# AcceleratedLED.net
KiCad netlist of a schematic drawn in EAGLE
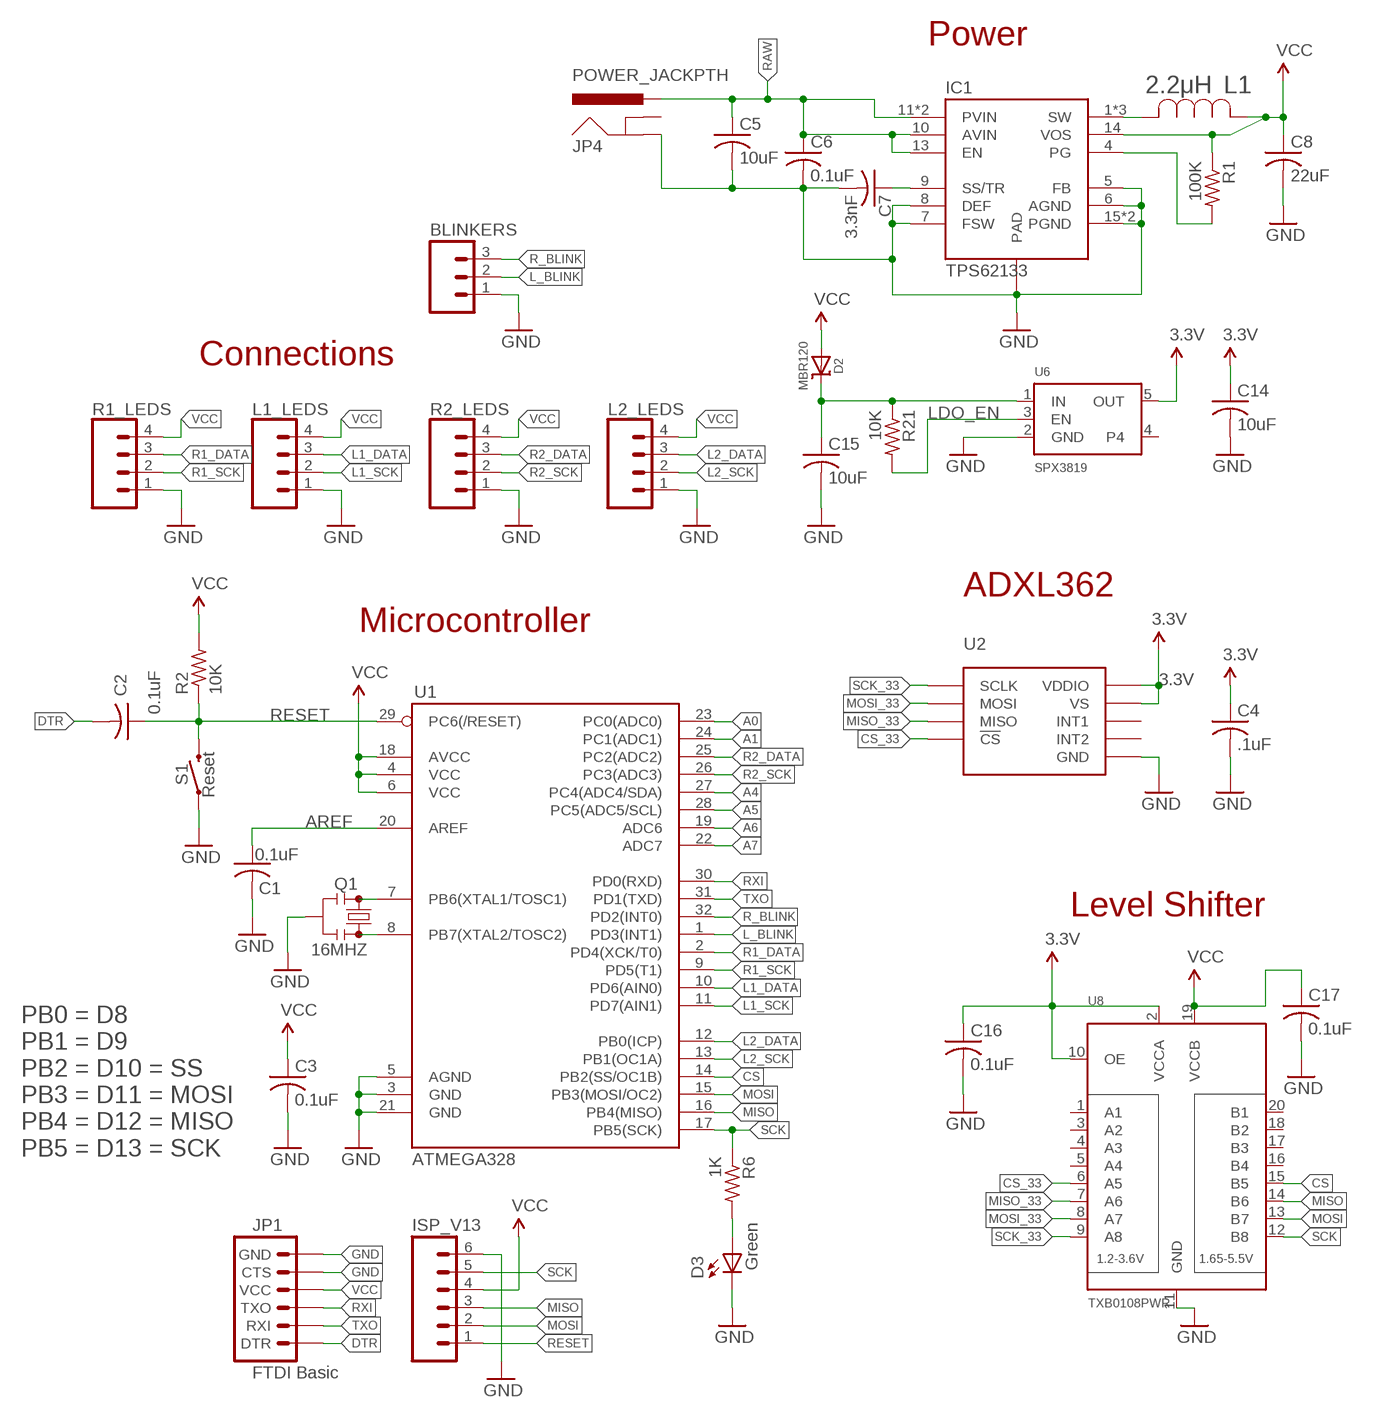
[diagram p0: schematic, sheet 1]

(export (version "E")
  (design (tool "Eeschema 10.0.6"))
  (components
    (comp (ref "BLINKERS")
      (value "M03JST-PTH")
      (footprint "eagle-import:JST-3-PTH")
      (libsource (lib "eagle-import") (part "M03JST-PTH"))
    )
    (comp (ref "C1")
      (value "0.1uF")
      (footprint "eagle-import:C0805")
      (libsource (lib "eagle-import") (part "C-USC0805"))
    )
    (comp (ref "C2")
      (value "0.1uF")
      (footprint "eagle-import:C0805")
      (libsource (lib "eagle-import") (part "C-USC0805"))
    )
    (comp (ref "C3")
      (value "0.1uF")
      (footprint "eagle-import:C0805")
      (libsource (lib "eagle-import") (part "C-USC0805"))
    )
    (comp (ref "C4")
      (value ".1uF")
      (footprint "eagle-import:C0805")
      (libsource (lib "eagle-import") (part "RemoteMotion_2810894_C-USC0805"))
    )
    (comp (ref "C5")
      (value "10uF")
      (footprint "eagle-import:C0805")
      (libsource (lib "eagle-import") (part "RemoteMotion_2810894_C-USC0805"))
    )
    (comp (ref "C6")
      (value "0.1uF")
      (footprint "eagle-import:C0805")
      (libsource (lib "eagle-import") (part "C-USC0805"))
    )
    (comp (ref "C7")
      (value "3.3nF")
      (footprint "eagle-import:C0805")
      (libsource (lib "eagle-import") (part "C-USC0805"))
    )
    (comp (ref "C8")
      (value "22uF")
      (footprint "eagle-import:C0805")
      (libsource (lib "eagle-import") (part "RemoteMotion_2810894_C-USC0805"))
    )
    (comp (ref "C14")
      (value "10uF")
      (footprint "eagle-import:C0805")
      (libsource (lib "eagle-import") (part "RemoteMotion_2810894_C-USC0805"))
    )
    (comp (ref "C15")
      (value "10uF")
      (footprint "eagle-import:C0805")
      (libsource (lib "eagle-import") (part "C-USC0805"))
    )
    (comp (ref "C16")
      (value "0.1uF")
      (footprint "eagle-import:C0805")
      (libsource (lib "eagle-import") (part "rcl_334_C-USC0805"))
    )
    (comp (ref "C17")
      (value "0.1uF")
      (footprint "eagle-import:C0805")
      (libsource (lib "eagle-import") (part "rcl_334_C-USC0805"))
    )
    (comp (ref "D2")
      (value "MBR120")
      (footprint "eagle-import:SOD-123")
      (libsource (lib "eagle-import") (part "DIODE-SCHOTTKYSOD-123"))
    )
    (comp (ref "D3")
      (value "Green")
      (footprint "eagle-import:CHIPLED_0805")
      (libsource (lib "eagle-import") (part "LEDCHIPLED_0805"))
    )
    (comp (ref "IC1")
      (value "TPS62133")
      (footprint "eagle-import:QFN16")
      (libsource (lib "eagle-import") (part "TPS62133"))
    )
    (comp (ref "ISP_V13")
      (value "M06SIP")
      (footprint "eagle-import:1X06")
      (libsource (lib "eagle-import") (part "M06SIP"))
    )
    (comp (ref "JP1")
      (value "FTDI Basic")
      (footprint "eagle-import:1X06")
      (libsource (lib "eagle-import") (part "ARDUINO_SERIAL_PROGRAMPTH"))
    )
    (comp (ref "JP4")
      (value "POWER_JACKPTH")
      (footprint "eagle-import:POWER_JACK_PTH")
      (libsource (lib "eagle-import") (part "POWER_JACKPTH"))
    )
    (comp (ref "L1")
      (value "2.2μH")
      (footprint "eagle-import:IND_IHLP-1212BZ-L")
      (fields (field (name "MANUFACTURER_PART_NUMBER") "IHLP1212BZER2R2M11"))
      (libsource (lib "eagle-import") (part "IHLP1212BZER2R2M11IND_IHLP-1212BZ-L"))
    )
    (comp (ref "L1_LEDS")
      (value "CONN_04JST-PTH")
      (footprint "eagle-import:JST-4-PTH")
      (libsource (lib "eagle-import") (part "CONN_04JST-PTH"))
    )
    (comp (ref "L2_LEDS")
      (value "CONN_04JST-PTH")
      (footprint "eagle-import:JST-4-PTH")
      (libsource (lib "eagle-import") (part "CONN_04JST-PTH"))
    )
    (comp (ref "Q1")
      (value "16MHZ")
      (footprint "eagle-import:RESONATOR-SMD")
      (libsource (lib "eagle-import") (part "RESONATOR16MHZ"))
    )
    (comp (ref "R1")
      (value "100K")
      (footprint "eagle-import:M0805")
      (libsource (lib "eagle-import") (part "R-US_M0805"))
    )
    (comp (ref "R1_LEDS")
      (value "CONN_04JST-PTH")
      (footprint "eagle-import:JST-4-PTH")
      (libsource (lib "eagle-import") (part "CONN_04JST-PTH"))
    )
    (comp (ref "R2")
      (value "10K")
      (footprint "eagle-import:M0805")
      (libsource (lib "eagle-import") (part "R-US_M0805"))
    )
    (comp (ref "R2_LEDS")
      (value "CONN_04JST-PTH")
      (footprint "eagle-import:JST-4-PTH")
      (libsource (lib "eagle-import") (part "CONN_04JST-PTH"))
    )
    (comp (ref "R6")
      (value "1K")
      (footprint "eagle-import:M0805")
      (libsource (lib "eagle-import") (part "R-US_M0805"))
    )
    (comp (ref "R21")
      (value "10K")
      (footprint "eagle-import:M0805")
      (libsource (lib "eagle-import") (part "R-US_M0805"))
    )
    (comp (ref "S1")
      (value "Reset")
      (footprint "eagle-import:TACTILE_SWITCH_SMD_5.2MM")
      (libsource (lib "eagle-import") (part "MOMENTARY-SWITCH-SPST-SMD-5.2-REDUNDANT"))
    )
    (comp (ref "U1")
      (value "ATMEGA328")
      (footprint "eagle-import:TQFP32-08")
      (libsource (lib "eagle-import") (part "ATMEGA168"))
    )
    (comp (ref "U2")
      (value "ADXL362ADXL362-1:1")
      (footprint "eagle-import:ADXL362-1_1")
      (libsource (lib "eagle-import") (part "ADXL362ADXL362-1{colon}1"))
    )
    (comp (ref "U6")
      (value "SPX3819")
      (footprint "eagle-import:SOT23-5")
      (libsource (lib "eagle-import") (part "VREG_SOT23-5"))
    )
    (comp (ref "U8")
      (value "TXB0108PWR")
      (footprint "eagle-import:TSSOP20")
      (libsource (lib "eagle-import") (part "TXB0108PWR"))
    )
  )
  (nets
    (net (code "1") (name "/AREF") (class "Default")
      (node (ref "C1") (pin "1") (pinfunction "1_1") (pintype "passive"))
      (node (ref "U1") (pin "20") (pinfunction "AREF_20") (pintype "bidirectional"))
    )
    (net (code "2") (name "/LDO_EN") (class "Default")
      (node (ref "R21") (pin "2") (pinfunction "2_2") (pintype "passive"))
      (node (ref "U6") (pin "3") (pinfunction "EN_3") (pintype "input"))
    )
    (net (code "3") (name "3.3V") (class "Default")
      (node (ref "C14") (pin "1") (pinfunction "1_1") (pintype "passive"))
      (node (ref "C16") (pin "1") (pinfunction "1_1") (pintype "passive"))
      (node (ref "C4") (pin "1") (pinfunction "1_1") (pintype "passive"))
      (node (ref "U2") (pin "P$1") (pinfunction "VDDIO_P$1") (pintype "bidirectional"))
      (node (ref "U2") (pin "P$14") (pinfunction "VS_P$14") (pintype "bidirectional"))
      (node (ref "U6") (pin "5") (pinfunction "OUT_5") (pintype "power_in"))
      (node (ref "U8") (pin "10") (pinfunction "OE_10") (pintype "bidirectional"))
      (node (ref "U8") (pin "2") (pinfunction "VCCA_2") (pintype "bidirectional"))
    )
    (net (code "4") (name "A0") (class "Default")
      (node (ref "U1") (pin "23") (pinfunction "PC0(ADC0)_23") (pintype "bidirectional"))
    )
    (net (code "5") (name "A1") (class "Default")
      (node (ref "U1") (pin "24") (pinfunction "PC1(ADC1)_24") (pintype "bidirectional"))
    )
    (net (code "6") (name "A4") (class "Default")
      (node (ref "U1") (pin "27") (pinfunction "PC4(ADC4/SDA)_27") (pintype "bidirectional"))
    )
    (net (code "7") (name "A5") (class "Default")
      (node (ref "U1") (pin "28") (pinfunction "PC5(ADC5/SCL)_28") (pintype "bidirectional"))
    )
    (net (code "8") (name "A6") (class "Default")
      (node (ref "U1") (pin "19") (pinfunction "ADC6_19") (pintype "bidirectional"))
    )
    (net (code "9") (name "A7") (class "Default")
      (node (ref "U1") (pin "22") (pinfunction "ADC7_22") (pintype "bidirectional"))
    )
    (net (code "10") (name "CS") (class "Default")
      (node (ref "U1") (pin "14") (pinfunction "PB2(SS/OC1B)_14") (pintype "bidirectional"))
      (node (ref "U8") (pin "15") (pinfunction "B5_15") (pintype "bidirectional"))
    )
    (net (code "11") (name "CS_33") (class "Default")
      (node (ref "U2") (pin "P$8") (pinfunction "~{CS}_P$8") (pintype "bidirectional"))
      (node (ref "U8") (pin "6") (pinfunction "A5_6") (pintype "bidirectional"))
    )
    (net (code "12") (name "DTR") (class "Default")
      (node (ref "C2") (pin "2") (pinfunction "2_2") (pintype "passive"))
      (node (ref "JP1") (pin "1") (pinfunction "DTR_1") (pintype "passive"))
    )
    (net (code "13") (name "GND") (class "Default")
      (node (ref "BLINKERS") (pin "1") (pinfunction "1_1") (pintype "passive"))
      (node (ref "C1") (pin "2") (pinfunction "2_2") (pintype "passive"))
      (node (ref "C14") (pin "2") (pinfunction "2_2") (pintype "passive"))
      (node (ref "C15") (pin "2") (pinfunction "2_2") (pintype "passive"))
      (node (ref "C16") (pin "2") (pinfunction "2_2") (pintype "passive"))
      (node (ref "C17") (pin "2") (pinfunction "2_2") (pintype "passive"))
      (node (ref "C3") (pin "2") (pinfunction "2_2") (pintype "passive"))
      (node (ref "C4") (pin "2") (pinfunction "2_2") (pintype "passive"))
      (node (ref "C5") (pin "2") (pinfunction "2_2") (pintype "passive"))
      (node (ref "C6") (pin "2") (pinfunction "2_2") (pintype "passive"))
      (node (ref "C7") (pin "2") (pinfunction "2_2") (pintype "passive"))
      (node (ref "C8") (pin "2") (pinfunction "2_2") (pintype "passive"))
      (node (ref "D3") (pin "C") (pinfunction "C_C") (pintype "passive"))
      (node (ref "IC1") (pin "15") (pinfunction "PGND_15") (pintype "bidirectional"))
      (node (ref "IC1") (pin "16") (pinfunction "PGND_16") (pintype "bidirectional"))
      (node (ref "IC1") (pin "5") (pinfunction "FB_5") (pintype "bidirectional"))
      (node (ref "IC1") (pin "6") (pinfunction "AGND_6") (pintype "bidirectional"))
      (node (ref "IC1") (pin "7") (pinfunction "FSW_7") (pintype "bidirectional"))
      (node (ref "IC1") (pin "8") (pinfunction "DEF_8") (pintype "bidirectional"))
      (node (ref "IC1") (pin "PAD") (pinfunction "PAD_PAD") (pintype "bidirectional"))
      (node (ref "ISP_V13") (pin "6") (pinfunction "6_6") (pintype "passive"))
      (node (ref "JP1") (pin "5") (pinfunction "CTS_5") (pintype "passive"))
      (node (ref "JP1") (pin "6") (pinfunction "GND_6") (pintype "passive"))
      (node (ref "JP4") (pin "GND") (pinfunction "GND_GND") (pintype "bidirectional"))
      (node (ref "L1_LEDS") (pin "1") (pinfunction "1_1") (pintype "passive"))
      (node (ref "L2_LEDS") (pin "1") (pinfunction "1_1") (pintype "passive"))
      (node (ref "Q1") (pin "2") (pinfunction "2_2") (pintype "passive"))
      (node (ref "R1_LEDS") (pin "1") (pinfunction "1_1") (pintype "passive"))
      (node (ref "R2_LEDS") (pin "1") (pinfunction "1_1") (pintype "passive"))
      (node (ref "S1") (pin "1") (pinfunction "1_1") (pintype "passive"))
      (node (ref "S1") (pin "2") (pinfunction "1_2") (pintype "passive"))
      (node (ref "U1") (pin "21") (pinfunction "GND_21") (pintype "bidirectional"))
      (node (ref "U1") (pin "3") (pinfunction "GND_3") (pintype "bidirectional"))
      (node (ref "U1") (pin "5") (pinfunction "AGND_5") (pintype "bidirectional"))
      (node (ref "U2") (pin "P$12") (pinfunction "GND_P$12") (pintype "bidirectional"))
      (node (ref "U2") (pin "P$13") (pinfunction "GND_P$13") (pintype "bidirectional"))
      (node (ref "U2") (pin "P$16") (pinfunction "GND_P$16") (pintype "bidirectional"))
      (node (ref "U6") (pin "2") (pinfunction "GND_2") (pintype "power_in"))
      (node (ref "U8") (pin "11") (pinfunction "GND_11") (pintype "bidirectional"))
    )
    (net (code "14") (name "L1_DATA") (class "Default")
      (node (ref "L1_LEDS") (pin "3") (pinfunction "3_3") (pintype "passive"))
      (node (ref "U1") (pin "10") (pinfunction "PD6(AIN0)_10") (pintype "bidirectional"))
    )
    (net (code "15") (name "L1_SCK") (class "Default")
      (node (ref "L1_LEDS") (pin "2") (pinfunction "2_2") (pintype "passive"))
      (node (ref "U1") (pin "11") (pinfunction "PD7(AIN1)_11") (pintype "bidirectional"))
    )
    (net (code "16") (name "L2_DATA") (class "Default")
      (node (ref "L2_LEDS") (pin "3") (pinfunction "3_3") (pintype "passive"))
      (node (ref "U1") (pin "12") (pinfunction "PB0(ICP)_12") (pintype "bidirectional"))
    )
    (net (code "17") (name "L2_SCK") (class "Default")
      (node (ref "L2_LEDS") (pin "2") (pinfunction "2_2") (pintype "passive"))
      (node (ref "U1") (pin "13") (pinfunction "PB1(OC1A)_13") (pintype "bidirectional"))
    )
    (net (code "18") (name "L_BLINK") (class "Default")
      (node (ref "BLINKERS") (pin "2") (pinfunction "2_2") (pintype "passive"))
      (node (ref "U1") (pin "1") (pinfunction "PD3(INT1)_1") (pintype "bidirectional"))
    )
    (net (code "19") (name "MISO") (class "Default")
      (node (ref "ISP_V13") (pin "3") (pinfunction "3_3") (pintype "passive"))
      (node (ref "U1") (pin "16") (pinfunction "PB4(MISO)_16") (pintype "bidirectional"))
      (node (ref "U8") (pin "14") (pinfunction "B6_14") (pintype "bidirectional"))
    )
    (net (code "20") (name "MISO_33") (class "Default")
      (node (ref "U2") (pin "P$7") (pinfunction "MISO_P$7") (pintype "bidirectional"))
      (node (ref "U8") (pin "7") (pinfunction "A6_7") (pintype "bidirectional"))
    )
    (net (code "21") (name "MOSI") (class "Default")
      (node (ref "ISP_V13") (pin "2") (pinfunction "2_2") (pintype "passive"))
      (node (ref "U1") (pin "15") (pinfunction "PB3(MOSI/OC2)_15") (pintype "bidirectional"))
      (node (ref "U8") (pin "13") (pinfunction "B7_13") (pintype "bidirectional"))
    )
    (net (code "22") (name "MOSI_33") (class "Default")
      (node (ref "U2") (pin "P$6") (pinfunction "MOSI_P$6") (pintype "bidirectional"))
      (node (ref "U8") (pin "8") (pinfunction "A7_8") (pintype "bidirectional"))
    )
    (net (code "23") (name "Net-(D3-PadA)") (class "Default")
      (node (ref "D3") (pin "A") (pinfunction "A_A") (pintype "passive"))
      (node (ref "R6") (pin "2") (pinfunction "2_2") (pintype "passive"))
    )
    (net (code "24") (name "Net-(IC1-PG)") (class "Default")
      (node (ref "IC1") (pin "4") (pinfunction "PG_4") (pintype "bidirectional"))
      (node (ref "R1") (pin "2") (pinfunction "2_2") (pintype "passive"))
    )
    (net (code "25") (name "Net-(IC1-SS{slash}TR)") (class "Default")
      (node (ref "C7") (pin "1") (pinfunction "1_1") (pintype "passive"))
      (node (ref "IC1") (pin "9") (pinfunction "SS/TR_9") (pintype "bidirectional"))
    )
    (net (code "26") (name "Net-(IC1-SW-Pad1)") (class "Default")
      (node (ref "IC1") (pin "1") (pinfunction "SW_1") (pintype "bidirectional"))
      (node (ref "IC1") (pin "2") (pinfunction "SW_2") (pintype "bidirectional"))
      (node (ref "IC1") (pin "3") (pinfunction "SW_3") (pintype "bidirectional"))
      (node (ref "L1") (pin "2") (pinfunction "2_2") (pintype "passive"))
    )
    (net (code "27") (name "Net-(U1-PB6(XTAL1{slash}TOSC1))") (class "Default")
      (node (ref "Q1") (pin "1") (pinfunction "1_1") (pintype "passive"))
      (node (ref "U1") (pin "7") (pinfunction "PB6(XTAL1/TOSC1)_7") (pintype "bidirectional"))
    )
    (net (code "28") (name "Net-(U1-PB7(XTAL2{slash}TOSC2))") (class "Default")
      (node (ref "Q1") (pin "3") (pinfunction "3_3") (pintype "passive"))
      (node (ref "U1") (pin "8") (pinfunction "PB7(XTAL2/TOSC2)_8") (pintype "bidirectional"))
    )
    (net (code "29") (name "Net-(U6-IN)") (class "Default")
      (node (ref "C15") (pin "1") (pinfunction "1_1") (pintype "passive"))
      (node (ref "D2") (pin "C") (pinfunction "C_C") (pintype "passive"))
      (node (ref "R21") (pin "1") (pinfunction "1_1") (pintype "passive"))
      (node (ref "U6") (pin "1") (pinfunction "IN_1") (pintype "power_in"))
    )
    (net (code "30") (name "R1_DATA") (class "Default")
      (node (ref "R1_LEDS") (pin "3") (pinfunction "3_3") (pintype "passive"))
      (node (ref "U1") (pin "2") (pinfunction "PD4(XCK/T0)_2") (pintype "bidirectional"))
    )
    (net (code "31") (name "R1_SCK") (class "Default")
      (node (ref "R1_LEDS") (pin "2") (pinfunction "2_2") (pintype "passive"))
      (node (ref "U1") (pin "9") (pinfunction "PD5(T1)_9") (pintype "bidirectional"))
    )
    (net (code "32") (name "R2_DATA") (class "Default")
      (node (ref "R2_LEDS") (pin "3") (pinfunction "3_3") (pintype "passive"))
      (node (ref "U1") (pin "25") (pinfunction "PC2(ADC2)_25") (pintype "bidirectional"))
    )
    (net (code "33") (name "R2_SCK") (class "Default")
      (node (ref "R2_LEDS") (pin "2") (pinfunction "2_2") (pintype "passive"))
      (node (ref "U1") (pin "26") (pinfunction "PC3(ADC3)_26") (pintype "bidirectional"))
    )
    (net (code "34") (name "RAW") (class "Default")
      (node (ref "C5") (pin "1") (pinfunction "1_1") (pintype "passive"))
      (node (ref "C6") (pin "1") (pinfunction "1_1") (pintype "passive"))
      (node (ref "IC1") (pin "10") (pinfunction "AVIN_10") (pintype "bidirectional"))
      (node (ref "IC1") (pin "11") (pinfunction "PVIN_11") (pintype "bidirectional"))
      (node (ref "IC1") (pin "12") (pinfunction "PVIN_12") (pintype "bidirectional"))
      (node (ref "IC1") (pin "13") (pinfunction "EN_13") (pintype "bidirectional"))
      (node (ref "JP4") (pin "PWR") (pinfunction "PWR_PWR") (pintype "bidirectional"))
    )
    (net (code "35") (name "RESET") (class "Default")
      (node (ref "C2") (pin "1") (pinfunction "1_1") (pintype "passive"))
      (node (ref "ISP_V13") (pin "1") (pinfunction "1_1") (pintype "passive"))
      (node (ref "R2") (pin "1") (pinfunction "1_1") (pintype "passive"))
      (node (ref "S1") (pin "3") (pinfunction "2_3") (pintype "passive"))
      (node (ref "S1") (pin "4") (pinfunction "2_4") (pintype "passive"))
      (node (ref "U1") (pin "29") (pinfunction "PC6(/RESET)_29") (pintype "bidirectional"))
    )
    (net (code "36") (name "RXI") (class "Default")
      (node (ref "JP1") (pin "3") (pinfunction "TXO_3") (pintype "passive"))
      (node (ref "U1") (pin "30") (pinfunction "PD0(RXD)_30") (pintype "bidirectional"))
    )
    (net (code "37") (name "R_BLINK") (class "Default")
      (node (ref "BLINKERS") (pin "3") (pinfunction "3_3") (pintype "passive"))
      (node (ref "U1") (pin "32") (pinfunction "PD2(INT0)_32") (pintype "bidirectional"))
    )
    (net (code "38") (name "SCK") (class "Default")
      (node (ref "ISP_V13") (pin "5") (pinfunction "5_5") (pintype "passive"))
      (node (ref "R6") (pin "1") (pinfunction "1_1") (pintype "passive"))
      (node (ref "U1") (pin "17") (pinfunction "PB5(SCK)_17") (pintype "bidirectional"))
      (node (ref "U8") (pin "12") (pinfunction "B8_12") (pintype "bidirectional"))
    )
    (net (code "39") (name "SCK_33") (class "Default")
      (node (ref "U2") (pin "P$4") (pinfunction "SCLK_P$4") (pintype "bidirectional"))
      (node (ref "U8") (pin "9") (pinfunction "A8_9") (pintype "bidirectional"))
    )
    (net (code "40") (name "TXO") (class "Default")
      (node (ref "JP1") (pin "2") (pinfunction "RXI_2") (pintype "passive"))
      (node (ref "U1") (pin "31") (pinfunction "PD1(TXD)_31") (pintype "bidirectional"))
    )
    (net (code "41") (name "VCC") (class "Default")
      (node (ref "C17") (pin "1") (pinfunction "1_1") (pintype "passive"))
      (node (ref "C3") (pin "1") (pinfunction "1_1") (pintype "passive"))
      (node (ref "C8") (pin "1") (pinfunction "1_1") (pintype "passive"))
      (node (ref "D2") (pin "A") (pinfunction "A_A") (pintype "passive"))
      (node (ref "IC1") (pin "14") (pinfunction "VOS_14") (pintype "bidirectional"))
      (node (ref "ISP_V13") (pin "4") (pinfunction "4_4") (pintype "passive"))
      (node (ref "JP1") (pin "4") (pinfunction "VCC_4") (pintype "passive"))
      (node (ref "L1") (pin "1") (pinfunction "1_1") (pintype "passive"))
      (node (ref "L1_LEDS") (pin "4") (pinfunction "4_4") (pintype "passive"))
      (node (ref "L2_LEDS") (pin "4") (pinfunction "4_4") (pintype "passive"))
      (node (ref "R1") (pin "1") (pinfunction "1_1") (pintype "passive"))
      (node (ref "R1_LEDS") (pin "4") (pinfunction "4_4") (pintype "passive"))
      (node (ref "R2") (pin "2") (pinfunction "2_2") (pintype "passive"))
      (node (ref "R2_LEDS") (pin "4") (pinfunction "4_4") (pintype "passive"))
      (node (ref "U1") (pin "18") (pinfunction "AVCC_18") (pintype "bidirectional"))
      (node (ref "U1") (pin "4") (pinfunction "VCC_4") (pintype "bidirectional"))
      (node (ref "U1") (pin "6") (pinfunction "VCC_6") (pintype "bidirectional"))
      (node (ref "U8") (pin "19") (pinfunction "VCCB_19") (pintype "bidirectional"))
    )
    (net (code "42") (name "unconnected-(JP4-PadGNDBREAK)") (class "Default")
      (node (ref "JP4") (pin "GNDBREAK") (pinfunction "GNDBREAK_GNDBREAK") (pintype "bidirectional"))
    )
    (net (code "43") (name "unconnected-(U2-INT1-PadP$11)") (class "Default")
      (node (ref "U2") (pin "P$11") (pinfunction "INT1_P$11") (pintype "bidirectional"))
    )
    (net (code "44") (name "unconnected-(U2-INT2-PadP$9)") (class "Default")
      (node (ref "U2") (pin "P$9") (pinfunction "INT2_P$9") (pintype "bidirectional"))
    )
    (net (code "45") (name "unconnected-(U6-P4-Pad4)") (class "Default")
      (node (ref "U6") (pin "4") (pinfunction "P4_4") (pintype "bidirectional"))
    )
    (net (code "46") (name "unconnected-(U8-A1-Pad1)") (class "Default")
      (node (ref "U8") (pin "1") (pinfunction "A1_1") (pintype "bidirectional"))
    )
    (net (code "47") (name "unconnected-(U8-A2-Pad3)") (class "Default")
      (node (ref "U8") (pin "3") (pinfunction "A2_3") (pintype "bidirectional"))
    )
    (net (code "48") (name "unconnected-(U8-A3-Pad4)") (class "Default")
      (node (ref "U8") (pin "4") (pinfunction "A3_4") (pintype "bidirectional"))
    )
    (net (code "49") (name "unconnected-(U8-A4-Pad5)") (class "Default")
      (node (ref "U8") (pin "5") (pinfunction "A4_5") (pintype "bidirectional"))
    )
    (net (code "50") (name "unconnected-(U8-B1-Pad20)") (class "Default")
      (node (ref "U8") (pin "20") (pinfunction "B1_20") (pintype "bidirectional"))
    )
    (net (code "51") (name "unconnected-(U8-B2-Pad18)") (class "Default")
      (node (ref "U8") (pin "18") (pinfunction "B2_18") (pintype "bidirectional"))
    )
    (net (code "52") (name "unconnected-(U8-B3-Pad17)") (class "Default")
      (node (ref "U8") (pin "17") (pinfunction "B3_17") (pintype "bidirectional"))
    )
    (net (code "53") (name "unconnected-(U8-B4-Pad16)") (class "Default")
      (node (ref "U8") (pin "16") (pinfunction "B4_16") (pintype "bidirectional"))
    )
  )
)
